# power_supply.net
KiCad netlist of a schematic drawn in Altium Designer
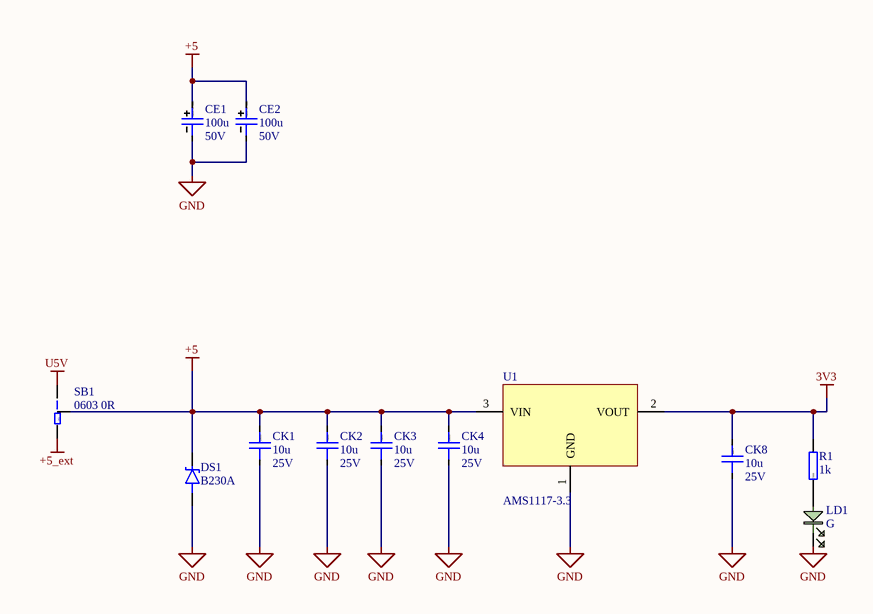
[diagram p0: power_supply.SchDoc]

(export (version "E")
  (design (tool "Eeschema 10.0.6"))
  (components
    (comp (ref "CE1")
      (value "100u")
      (footprint "CAPAE830X1100N")
      (description "100uF 50V ±20% SMD,D8xL10.2mm Aluminum Electrolytic Capacitors - SMD ROHS")
      (fields
        (field (name "JLCPCB PART") "C3352")
        (field (name "TME PART") "CK1H107M08010VR")
        (field (name "VOLTAGE RATING") "50V")
      )
      (libsource (lib "Kubikova ultra knihovna") (part "Cap el 100u 50V"))
    )
    (comp (ref "CE2")
      (value "100u")
      (footprint "CAPAE830X1100N")
      (description "100uF 50V ±20% SMD,D8xL10.2mm Aluminum Electrolytic Capacitors - SMD ROHS")
      (fields
        (field (name "JLCPCB PART") "C3352")
        (field (name "TME PART") "CK1H107M08010VR")
        (field (name "VOLTAGE RATING") "50V")
      )
      (libsource (lib "Kubikova ultra knihovna") (part "Cap el 100u 50V"))
    )
    (comp (ref "CK1")
      (value "10u")
      (footprint "CAP0805")
      (description "25V 10uF X5R ±10% 0805 Multilayer Ceramic Capacitors MLCC - SMD/SMT ROHS")
      (fields (field (name "JLCPCB PART") "C15850") (field (name "VOLTAGE RATING") "25V"))
      (libsource (lib "Kubikova ultra knihovna") (part "Cap 10u 0805"))
    )
    (comp (ref "CK2")
      (value "10u")
      (footprint "CAP0805")
      (description "25V 10uF X5R ±10% 0805 Multilayer Ceramic Capacitors MLCC - SMD/SMT ROHS")
      (fields (field (name "JLCPCB PART") "C15850") (field (name "VOLTAGE RATING") "25V"))
      (libsource (lib "Kubikova ultra knihovna") (part "Cap 10u 0805"))
    )
    (comp (ref "CK3")
      (value "10u")
      (footprint "CAP0805")
      (description "25V 10uF X5R ±10% 0805 Multilayer Ceramic Capacitors MLCC - SMD/SMT ROHS")
      (fields (field (name "JLCPCB PART") "C15850") (field (name "VOLTAGE RATING") "25V"))
      (libsource (lib "Kubikova ultra knihovna") (part "Cap 10u 0805"))
    )
    (comp (ref "CK4")
      (value "10u")
      (footprint "CAP0805")
      (description "25V 10uF X5R ±10% 0805 Multilayer Ceramic Capacitors MLCC - SMD/SMT ROHS")
      (fields (field (name "JLCPCB PART") "C15850") (field (name "VOLTAGE RATING") "25V"))
      (libsource (lib "Kubikova ultra knihovna") (part "Cap 10u 0805"))
    )
    (comp (ref "CK8")
      (value "10u")
      (footprint "CAP0805")
      (description "25V 10uF X5R ±10% 0805 Multilayer Ceramic Capacitors MLCC - SMD/SMT ROHS")
      (fields (field (name "JLCPCB PART") "C15850") (field (name "VOLTAGE RATING") "25V"))
      (libsource (lib "Kubikova ultra knihovna") (part "Cap 10u 0805"))
    )
    (comp (ref "DS1")
      (value "B230A")
      (footprint "DIOM4326X23M")
      (description "30V 500mV@2A 2A SMA(DO-214AC) Schottky Diodes ROHS")
      (fields (field (name "JLCPCB PART") "C12889"))
      (libsource (lib "Kubikova ultra knihovna") (part "B230A-13-F"))
    )
    (comp (ref "LD1")
      (value "G")
      (footprint "0603_LED_G")
      (description "0603 Green Led")
      (fields (field (name "JLCPCB PART") "C22371297"))
      (libsource (lib "Kubikova ultra knihovna") (part "LED G 0603"))
    )
    (comp (ref "R1")
      (value "1k")
      (footprint "RESC2012X06N(SMR0805)")
      (description "125mW Thick Film Resistors 150V ±100ppm/℃ ±1% 1kΩ 0805 Chip Resistor - Surface Mount ROHS")
      (fields (field (name "JLCPCB PART") "C17513") (field (name "AUTHOR") "JP/27.03.2014"))
      (libsource (lib "Kubikova ultra knihovna") (part "Res 1k 0805"))
    )
    (comp (ref "SB1")
      (value "0603 0R")
      (footprint "Solder T bridge 0603")
      (fields (field (name "JLCPCB PART") "C21189"))
      (libsource (lib "Kubikova ultra knihovna") (part "0R T-junction"))
    )
    (comp (ref "U1")
      (value "AMS1117-3.3")
      (footprint "SOT230P700X180-4M")
      (fields (field (name "JLCPCB PART") "C6186"))
      (libsource (lib "Kubikova ultra knihovna") (part "AMS1117-3.3"))
    )
  )
  (nets
    (net (code "1") (name "+5") (class "Default")
      (node (ref "CE1") (pin "1") (pinfunction "1_1") (pintype "passive"))
      (node (ref "CE2") (pin "1") (pinfunction "1_1") (pintype "passive"))
      (node (ref "CK1") (pin "1") (pinfunction "1_1") (pintype "passive"))
      (node (ref "CK2") (pin "1") (pinfunction "1_1") (pintype "passive"))
      (node (ref "CK3") (pin "1") (pinfunction "1_1") (pintype "passive"))
      (node (ref "CK4") (pin "1") (pinfunction "1_1") (pintype "passive"))
      (node (ref "DS1") (pin "1") (pinfunction "1_1") (pintype "passive"))
      (node (ref "SB1") (pin "2") (pinfunction "2_2") (pintype "passive"))
      (node (ref "U1") (pin "3") (pinfunction "VIN_3") (pintype "power_in"))
    )
    (net (code "2") (name "+5_ext") (class "Default")
      (node (ref "SB1") (pin "3") (pinfunction "3_3") (pintype "passive"))
    )
    (net (code "3") (name "3V3") (class "Default")
      (node (ref "CK8") (pin "1") (pinfunction "1_1") (pintype "passive"))
      (node (ref "R1") (pin "1") (pinfunction "1_1") (pintype "passive"))
      (node (ref "U1") (pin "2") (pinfunction "VOUT_2") (pintype "power_in"))
    )
    (net (code "4") (name "GND") (class "Default")
      (node (ref "CE1") (pin "2") (pinfunction "2_2") (pintype "passive"))
      (node (ref "CE2") (pin "2") (pinfunction "2_2") (pintype "passive"))
      (node (ref "CK1") (pin "2") (pinfunction "2_2") (pintype "passive"))
      (node (ref "CK2") (pin "2") (pinfunction "2_2") (pintype "passive"))
      (node (ref "CK3") (pin "2") (pinfunction "2_2") (pintype "passive"))
      (node (ref "CK4") (pin "2") (pinfunction "2_2") (pintype "passive"))
      (node (ref "CK8") (pin "2") (pinfunction "2_2") (pintype "passive"))
      (node (ref "DS1") (pin "2") (pinfunction "2_2") (pintype "passive"))
      (node (ref "LD1") (pin "2") (pintype "passive"))
      (node (ref "U1") (pin "1") (pinfunction "GND_1") (pintype "power_in"))
    )
    (net (code "5") (name "Net-(LD1-Pad1)") (class "Default")
      (node (ref "LD1") (pin "1") (pintype "passive"))
      (node (ref "R1") (pin "2") (pinfunction "2_2") (pintype "passive"))
    )
    (net (code "6") (name "U5V") (class "Default")
      (node (ref "SB1") (pin "1") (pinfunction "1_1") (pintype "passive"))
    )
  )
)
